# Sheet1.net
KiCad netlist of a schematic drawn in Altium Designer
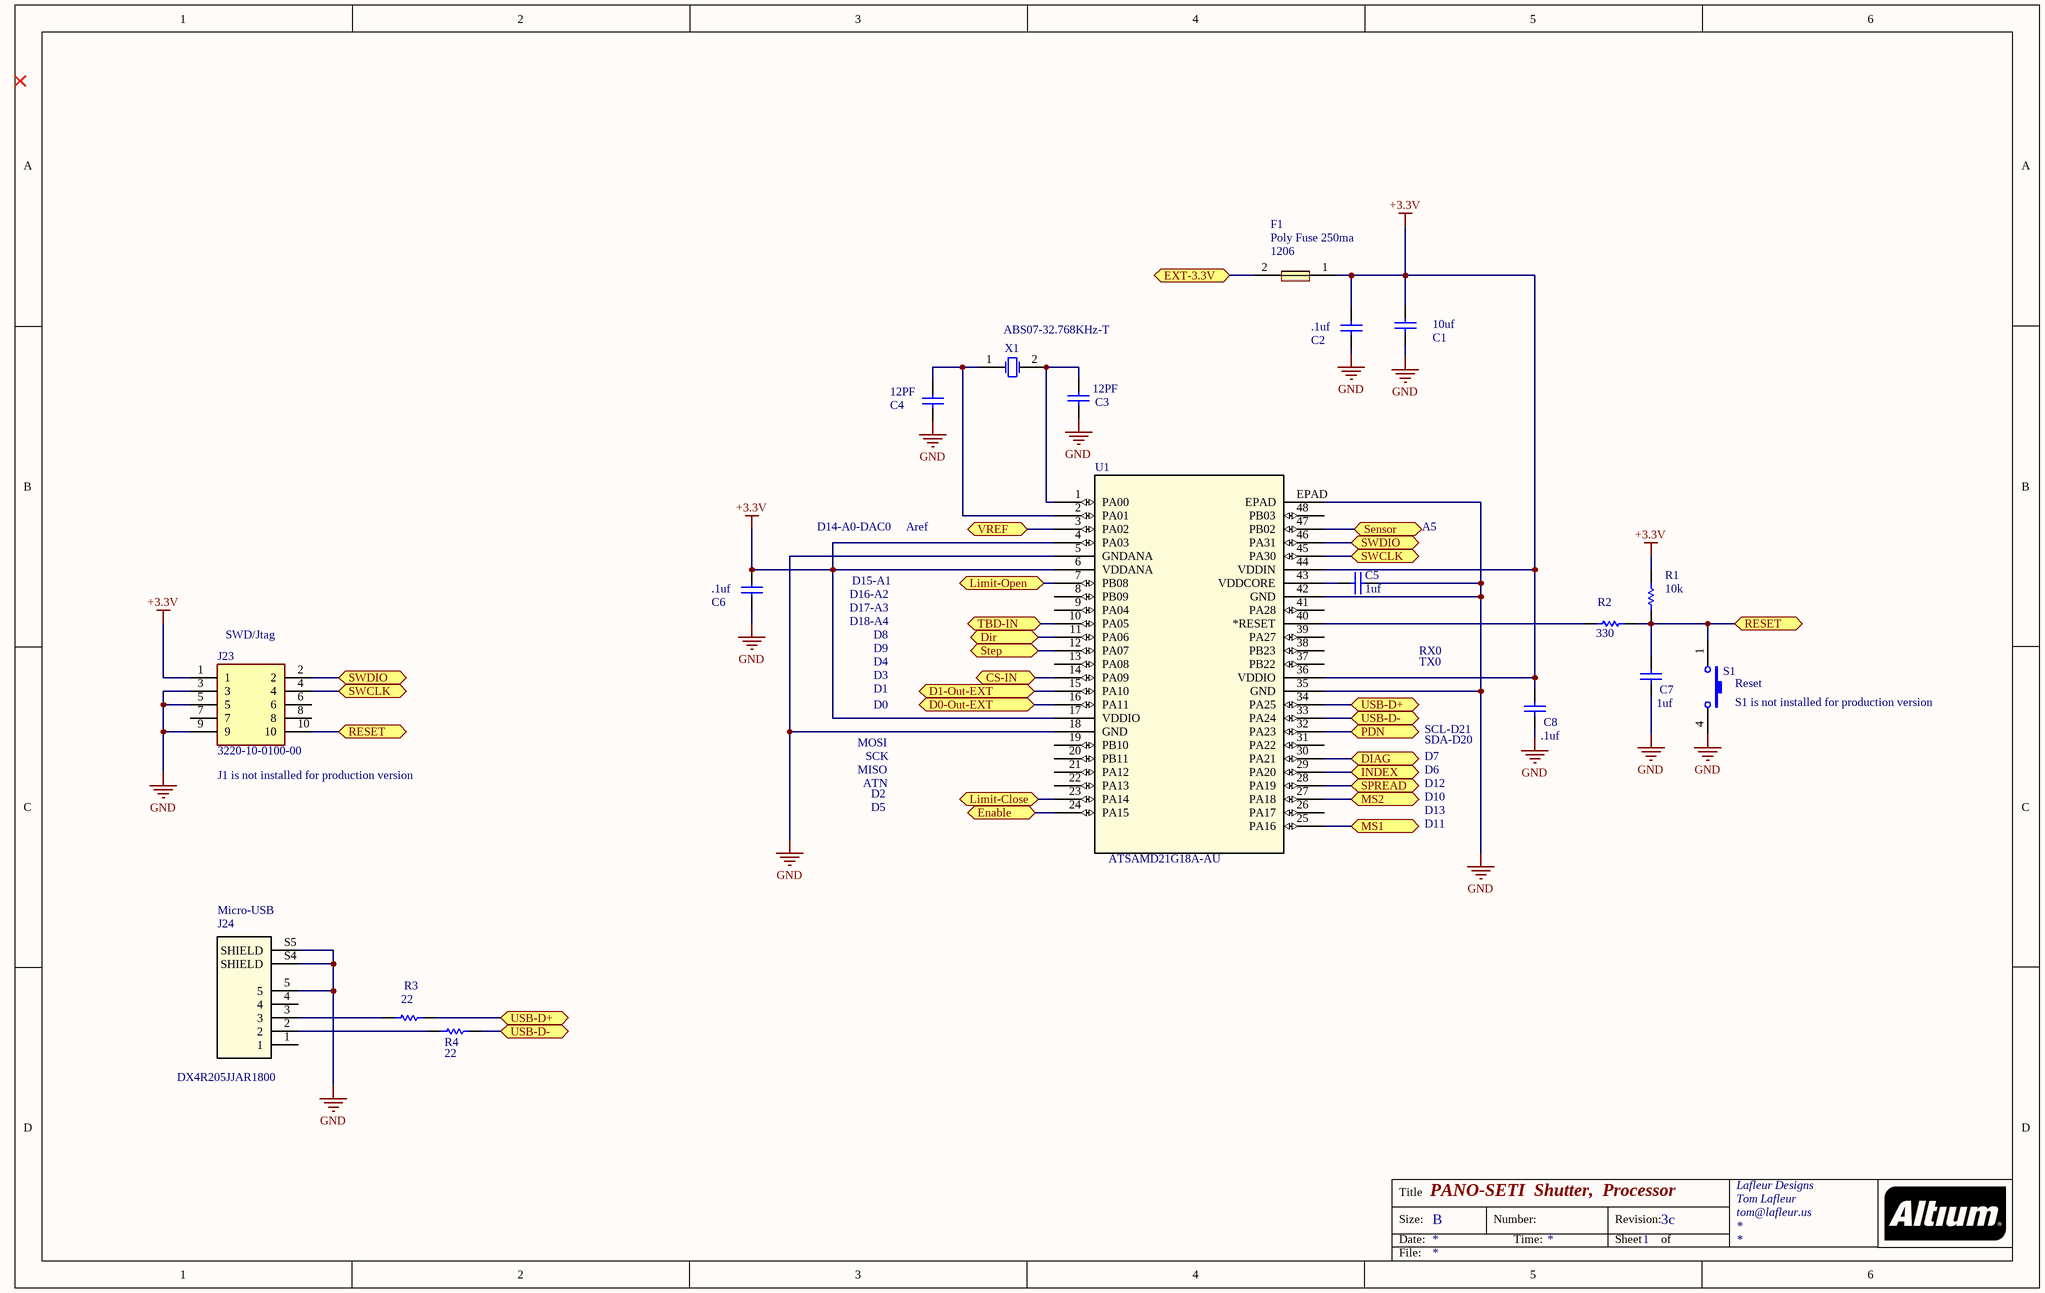
[diagram p0: Sheet1.SchDoc]

(export (version "E")
  (design (tool "Eeschema 10.0.6"))
  (components
    (comp (ref "C1")
      (value "10uf")
      (footprint "6-0805")
      (description "Capacitor")
      (libsource (lib "Winmor-Demo-R2") (part "CAP_2"))
    )
    (comp (ref "C2")
      (value ".1uf")
      (footprint "6-0805")
      (description "Capacitor")
      (libsource (lib "Winmor-Demo-R2") (part "CAP_2"))
    )
    (comp (ref "C3")
      (value "12PF")
      (footprint "6-0805")
      (description "Capacitor")
      (libsource (lib "Winmor-Demo-R2") (part "CAP_2"))
    )
    (comp (ref "C4")
      (value "12PF")
      (footprint "6-0805")
      (description "Capacitor")
      (libsource (lib "Winmor-Demo-R2") (part "CAP_2"))
    )
    (comp (ref "C5")
      (value "1uf")
      (footprint "6-0805")
      (description "Capacitor")
      (libsource (lib "Winmor-Demo-R2") (part "CAP_2"))
    )
    (comp (ref "C6")
      (value ".1uf")
      (footprint "6-0805")
      (description "Capacitor")
      (libsource (lib "Winmor-Demo-R2") (part "CAP_2"))
    )
    (comp (ref "C7")
      (value "1uf")
      (footprint "6-0805")
      (description "Capacitor")
      (libsource (lib "Winmor-Demo-R2") (part "CAP_2"))
    )
    (comp (ref "C8")
      (value ".1uf")
      (footprint "6-0805")
      (description "Capacitor")
      (libsource (lib "Winmor-Demo-R2") (part "CAP_2"))
    )
    (comp (ref "F1")
      (value "Poly Fuse 250ma")
      (footprint "8-1206")
      (description "Poly Fuse")
      (libsource (lib "N2K Project") (part "Poly Fuse"))
    )
    (comp (ref "J23")
      (value "3220-10-0100-00")
      (footprint "SHDR10W41P127_2X5_1265X510X565P")
      (description "Connector")
      (libsource (lib "*") (part "3220-10-0100-00"))
    )
    (comp (ref "J24")
      (value "DX4R205JJAR1800")
      (footprint "*JAE_DX4R205JJAR1800_DX4R205JJAR1800(Primary)")
      (description "DX4 series, receptacle, on-board, right-angle standard mount, surface mount")
      (fields (field (name "MF") "JAE Electronics") (field (name "DIGI-KEY_PART_NUMBER") "670-2677-1-ND"))
      (libsource (lib "Seti-Controler_5") (part "DX4R205JJAR1800"))
    )
    (comp (ref "R1")
      (value "10k")
      (footprint "6-0805")
      (description "Precision Thick Film Chip Resistor, 10 Ohm to 2.2M Ohm Range, 1% Tolerance, 1206 Size, 0.125 W")
      (fields (field (name "PUBLISHER") "Altium Limited"))
      (libsource (lib "N2K Project") (part "ERJ8EN"))
    )
    (comp (ref "R2")
      (value "330")
      (footprint "6-0805")
      (description "Precision Thick Film Chip Resistor, 10 Ohm to 2.2M Ohm Range, 1% Tolerance, 1206 Size, 0.125 W")
      (fields (field (name "PUBLISHER") "Altium Limited"))
      (libsource (lib "N2K Project") (part "ERJ8EN"))
    )
    (comp (ref "R3")
      (value "22")
      (footprint "6-0805")
      (description "Precision Thick Film Chip Resistor, 10 Ohm to 2.2M Ohm Range, 1% Tolerance, 1206 Size, 0.125 W")
      (fields (field (name "PUBLISHER") "Altium Limited"))
      (libsource (lib "N2K Project") (part "ERJ8EN"))
    )
    (comp (ref "R4")
      (value "22")
      (footprint "6-0805")
      (description "Precision Thick Film Chip Resistor, 10 Ohm to 2.2M Ohm Range, 1% Tolerance, 1206 Size, 0.125 W")
      (fields (field (name "PUBLISHER") "Altium Limited"))
      (libsource (lib "N2K Project") (part "ERJ8EN"))
    )
    (comp (ref "S1")
      (value "Reset")
      (footprint "SamacSys:KMR_2")
      (description "Switch")
      (fields (field (name "PUBLISHER") "Altium Limited"))
      (libsource (lib "Miscellaneous Devices") (part "SW-PB"))
    )
    (comp (ref "U1")
      (value "ATSAMD21G18A-AU")
      (footprint "TQFP48_7x7MC")
      (description "No Description Available")
      (fields (field (name "COPYRIGHT") "Copyright (C) 2018 Accelerated Designs. All rights reserved"))
      (libsource (lib "ATSAMD21G18") (part "ATSAMD21G18A-AU"))
    )
    (comp (ref "X1")
      (value "ABS07-32.768KHz-T")
      (footprint "ABRA-ABS07-2_V")
      (description "Crystal, 32.768 kHz, 12.5 pF, -40 to 85 degC, SMD Low Profile 3.2 x 1.5 x 0.9 mm, Tape and Reel")
      (fields (field (name "MANUFACTURER") "Abracon"))
      (libsource (lib "Altium Content Vault") (part "ABRA-ABS07-2"))
    )
  )
  (nets
    (net (code "1") (name "+3.3V") (class "Default")
      (node (ref "C1") (pin "1") (pinfunction "1_1") (pintype "passive"))
      (node (ref "C2") (pin "1") (pinfunction "1_1") (pintype "passive"))
      (node (ref "C6") (pin "1") (pinfunction "1_1") (pintype "passive"))
      (node (ref "C8") (pin "1") (pinfunction "1_1") (pintype "passive"))
      (node (ref "F1") (pin "1") (pinfunction "1_1") (pintype "passive"))
      (node (ref "J23") (pin "1") (pinfunction "1_1") (pintype "passive"))
      (node (ref "R1") (pin "1") (pinfunction "1_1") (pintype "passive"))
      (node (ref "U1") (pin "17") (pinfunction "VDDIO_17") (pintype "power_in"))
      (node (ref "U1") (pin "36") (pinfunction "VDDIO_36") (pintype "power_in"))
      (node (ref "U1") (pin "4") (pinfunction "PA03_4") (pintype "bidirectional"))
      (node (ref "U1") (pin "44") (pinfunction "VDDIN_44") (pintype "power_in"))
      (node (ref "U1") (pin "6") (pinfunction "VDDANA_6") (pintype "power_in"))
    )
    (net (code "2") (name "/CS-IN") (class "Default")
      (node (ref "U1") (pin "14") (pinfunction "PA09_14") (pintype "bidirectional"))
    )
    (net (code "3") (name "/D0-Out-EXT") (class "Default")
      (node (ref "U1") (pin "16") (pinfunction "PA11_16") (pintype "bidirectional"))
    )
    (net (code "4") (name "/D1-Out-EXT") (class "Default")
      (node (ref "U1") (pin "15") (pinfunction "PA10_15") (pintype "bidirectional"))
    )
    (net (code "5") (name "/DIAG") (class "Default")
      (node (ref "U1") (pin "30") (pinfunction "PA21_30") (pintype "bidirectional"))
    )
    (net (code "6") (name "/Dir") (class "Default")
      (node (ref "U1") (pin "11") (pinfunction "PA06_11") (pintype "bidirectional"))
    )
    (net (code "7") (name "/EXT-3.3V") (class "Default")
      (node (ref "F1") (pin "2") (pinfunction "2_2") (pintype "passive"))
    )
    (net (code "8") (name "/Enable") (class "Default")
      (node (ref "U1") (pin "24") (pinfunction "PA15_24") (pintype "bidirectional"))
    )
    (net (code "9") (name "/INDEX") (class "Default")
      (node (ref "U1") (pin "29") (pinfunction "PA20_29") (pintype "bidirectional"))
    )
    (net (code "10") (name "/Limit-Close") (class "Default")
      (node (ref "U1") (pin "23") (pinfunction "PA14_23") (pintype "bidirectional"))
    )
    (net (code "11") (name "/Limit-Open") (class "Default")
      (node (ref "U1") (pin "7") (pinfunction "PB08_7") (pintype "bidirectional"))
    )
    (net (code "12") (name "/MS1") (class "Default")
      (node (ref "U1") (pin "25") (pinfunction "PA16_25") (pintype "bidirectional"))
    )
    (net (code "13") (name "/MS2") (class "Default")
      (node (ref "U1") (pin "27") (pinfunction "PA18_27") (pintype "bidirectional"))
    )
    (net (code "14") (name "/PDN") (class "Default")
      (node (ref "U1") (pin "32") (pinfunction "PA23_32") (pintype "bidirectional"))
    )
    (net (code "15") (name "/RESET") (class "Default")
      (node (ref "C7") (pin "1") (pinfunction "1_1") (pintype "passive"))
      (node (ref "J23") (pin "10") (pinfunction "10_10") (pintype "passive"))
      (node (ref "R1") (pin "2") (pinfunction "2_2") (pintype "passive"))
      (node (ref "R2") (pin "2") (pinfunction "2_2") (pintype "passive"))
      (node (ref "S1") (pin "1") (pinfunction "1_1") (pintype "passive"))
    )
    (net (code "16") (name "/SPREAD") (class "Default")
      (node (ref "U1") (pin "28") (pinfunction "PA19_28") (pintype "bidirectional"))
    )
    (net (code "17") (name "/SWCLK") (class "Default")
      (node (ref "J23") (pin "4") (pinfunction "4_4") (pintype "passive"))
      (node (ref "U1") (pin "45") (pinfunction "PA30_45") (pintype "bidirectional"))
    )
    (net (code "18") (name "/SWDIO") (class "Default")
      (node (ref "J23") (pin "2") (pinfunction "2_2") (pintype "passive"))
      (node (ref "U1") (pin "46") (pinfunction "PA31_46") (pintype "bidirectional"))
    )
    (net (code "19") (name "/Sensor") (class "Default")
      (node (ref "U1") (pin "47") (pinfunction "PB02_47") (pintype "bidirectional"))
    )
    (net (code "20") (name "/Step") (class "Default")
      (node (ref "U1") (pin "12") (pinfunction "PA07_12") (pintype "bidirectional"))
    )
    (net (code "21") (name "/TBD-IN") (class "Default")
      (node (ref "U1") (pin "10") (pinfunction "PA05_10") (pintype "bidirectional"))
    )
    (net (code "22") (name "/USB-D+") (class "Default")
      (node (ref "R3") (pin "2") (pinfunction "2_2") (pintype "passive"))
      (node (ref "U1") (pin "34") (pinfunction "PA25_34") (pintype "bidirectional"))
    )
    (net (code "23") (name "/USB-D-") (class "Default")
      (node (ref "R4") (pin "2") (pinfunction "2_2") (pintype "passive"))
      (node (ref "U1") (pin "33") (pinfunction "PA24_33") (pintype "bidirectional"))
    )
    (net (code "24") (name "/VREF") (class "Default")
      (node (ref "U1") (pin "3") (pinfunction "PA02_3") (pintype "bidirectional"))
    )
    (net (code "25") (name "GND") (class "Default")
      (node (ref "C1") (pin "2") (pinfunction "2_2") (pintype "passive"))
      (node (ref "C2") (pin "2") (pinfunction "2_2") (pintype "passive"))
      (node (ref "C3") (pin "2") (pinfunction "2_2") (pintype "passive"))
      (node (ref "C4") (pin "2") (pinfunction "2_2") (pintype "passive"))
      (node (ref "C5") (pin "2") (pinfunction "2_2") (pintype "passive"))
      (node (ref "C6") (pin "2") (pinfunction "2_2") (pintype "passive"))
      (node (ref "C7") (pin "2") (pinfunction "2_2") (pintype "passive"))
      (node (ref "C8") (pin "2") (pinfunction "2_2") (pintype "passive"))
      (node (ref "J23") (pin "3") (pinfunction "3_3") (pintype "passive"))
      (node (ref "J23") (pin "5") (pinfunction "5_5") (pintype "passive"))
      (node (ref "J23") (pin "9") (pinfunction "9_9") (pintype "passive"))
      (node (ref "J24") (pin "5") (pinfunction "5_5") (pintype "passive"))
      (node (ref "J24") (pin "S4") (pinfunction "SHIELD_S4") (pintype "passive"))
      (node (ref "J24") (pin "S5") (pinfunction "SHIELD_S5") (pintype "passive"))
      (node (ref "S1") (pin "4") (pinfunction "4_4") (pintype "passive"))
      (node (ref "U1") (pin "18") (pinfunction "GND_18") (pintype "passive"))
      (node (ref "U1") (pin "35") (pinfunction "GND_35") (pintype "passive"))
      (node (ref "U1") (pin "42") (pinfunction "GND_42") (pintype "passive"))
      (node (ref "U1") (pin "5") (pinfunction "GNDANA_5") (pintype "passive"))
      (node (ref "U1") (pin "EPAD") (pinfunction "EPAD_EPAD") (pintype "passive"))
    )
    (net (code "26") (name "Net-(J24-Pad2)") (class "Default")
      (node (ref "J24") (pin "2") (pinfunction "2_2") (pintype "passive"))
      (node (ref "R4") (pin "1") (pinfunction "1_1") (pintype "passive"))
    )
    (net (code "27") (name "Net-(J24-Pad3)") (class "Default")
      (node (ref "J24") (pin "3") (pinfunction "3_3") (pintype "passive"))
      (node (ref "R3") (pin "1") (pinfunction "1_1") (pintype "passive"))
    )
    (net (code "28") (name "Net-(U1-*RESET)") (class "Default")
      (node (ref "R2") (pin "1") (pinfunction "1_1") (pintype "passive"))
      (node (ref "U1") (pin "40") (pinfunction "*RESET_40") (pintype "passive"))
    )
    (net (code "29") (name "Net-(U1-PA00)") (class "Default")
      (node (ref "C3") (pin "1") (pinfunction "1_1") (pintype "passive"))
      (node (ref "U1") (pin "1") (pinfunction "PA00_1") (pintype "bidirectional"))
      (node (ref "X1") (pin "2") (pinfunction "X2_2") (pintype "passive"))
    )
    (net (code "30") (name "Net-(U1-PA01)") (class "Default")
      (node (ref "C4") (pin "1") (pinfunction "1_1") (pintype "passive"))
      (node (ref "U1") (pin "2") (pinfunction "PA01_2") (pintype "bidirectional"))
      (node (ref "X1") (pin "1") (pinfunction "X1_1") (pintype "passive"))
    )
    (net (code "31") (name "Net-(U1-VDDCORE)") (class "Default")
      (node (ref "C5") (pin "1") (pinfunction "1_1") (pintype "passive"))
      (node (ref "U1") (pin "43") (pinfunction "VDDCORE_43") (pintype "power_in"))
    )
    (net (code "32") (name "unconnected-(J23-Pad6)") (class "Default")
      (node (ref "J23") (pin "6") (pinfunction "6_6") (pintype "passive"))
    )
    (net (code "33") (name "unconnected-(J23-Pad7)") (class "Default")
      (node (ref "J23") (pin "7") (pinfunction "7_7") (pintype "passive"))
    )
    (net (code "34") (name "unconnected-(J23-Pad8)") (class "Default")
      (node (ref "J23") (pin "8") (pinfunction "8_8") (pintype "passive"))
    )
    (net (code "35") (name "unconnected-(J24-Pad1)") (class "Default")
      (node (ref "J24") (pin "1") (pinfunction "1_1") (pintype "passive"))
    )
    (net (code "36") (name "unconnected-(J24-Pad4)") (class "Default")
      (node (ref "J24") (pin "4") (pinfunction "4_4") (pintype "passive"))
    )
    (net (code "37") (name "unconnected-(U1-PA04-Pad9)") (class "Default")
      (node (ref "U1") (pin "9") (pinfunction "PA04_9") (pintype "bidirectional"))
    )
    (net (code "38") (name "unconnected-(U1-PA08-Pad13)") (class "Default")
      (node (ref "U1") (pin "13") (pinfunction "PA08_13") (pintype "bidirectional"))
    )
    (net (code "39") (name "unconnected-(U1-PA12-Pad21)") (class "Default")
      (node (ref "U1") (pin "21") (pinfunction "PA12_21") (pintype "bidirectional"))
    )
    (net (code "40") (name "unconnected-(U1-PA13-Pad22)") (class "Default")
      (node (ref "U1") (pin "22") (pinfunction "PA13_22") (pintype "bidirectional"))
    )
    (net (code "41") (name "unconnected-(U1-PA17-Pad26)") (class "Default")
      (node (ref "U1") (pin "26") (pinfunction "PA17_26") (pintype "bidirectional"))
    )
    (net (code "42") (name "unconnected-(U1-PA22-Pad31)") (class "Default")
      (node (ref "U1") (pin "31") (pinfunction "PA22_31") (pintype "bidirectional"))
    )
    (net (code "43") (name "unconnected-(U1-PA27-Pad39)") (class "Default")
      (node (ref "U1") (pin "39") (pinfunction "PA27_39") (pintype "bidirectional"))
    )
    (net (code "44") (name "unconnected-(U1-PA28-Pad41)") (class "Default")
      (node (ref "U1") (pin "41") (pinfunction "PA28_41") (pintype "bidirectional"))
    )
    (net (code "45") (name "unconnected-(U1-PB03-Pad48)") (class "Default")
      (node (ref "U1") (pin "48") (pinfunction "PB03_48") (pintype "bidirectional"))
    )
    (net (code "46") (name "unconnected-(U1-PB09-Pad8)") (class "Default")
      (node (ref "U1") (pin "8") (pinfunction "PB09_8") (pintype "bidirectional"))
    )
    (net (code "47") (name "unconnected-(U1-PB10-Pad19)") (class "Default")
      (node (ref "U1") (pin "19") (pinfunction "PB10_19") (pintype "bidirectional"))
    )
    (net (code "48") (name "unconnected-(U1-PB11-Pad20)") (class "Default")
      (node (ref "U1") (pin "20") (pinfunction "PB11_20") (pintype "bidirectional"))
    )
    (net (code "49") (name "unconnected-(U1-PB22-Pad37)") (class "Default")
      (node (ref "U1") (pin "37") (pinfunction "PB22_37") (pintype "bidirectional"))
    )
    (net (code "50") (name "unconnected-(U1-PB23-Pad38)") (class "Default")
      (node (ref "U1") (pin "38") (pinfunction "PB23_38") (pintype "bidirectional"))
    )
  )
)
